# ClimaSens-Touch.net
KiCad netlist of a schematic drawn in Altium Designer
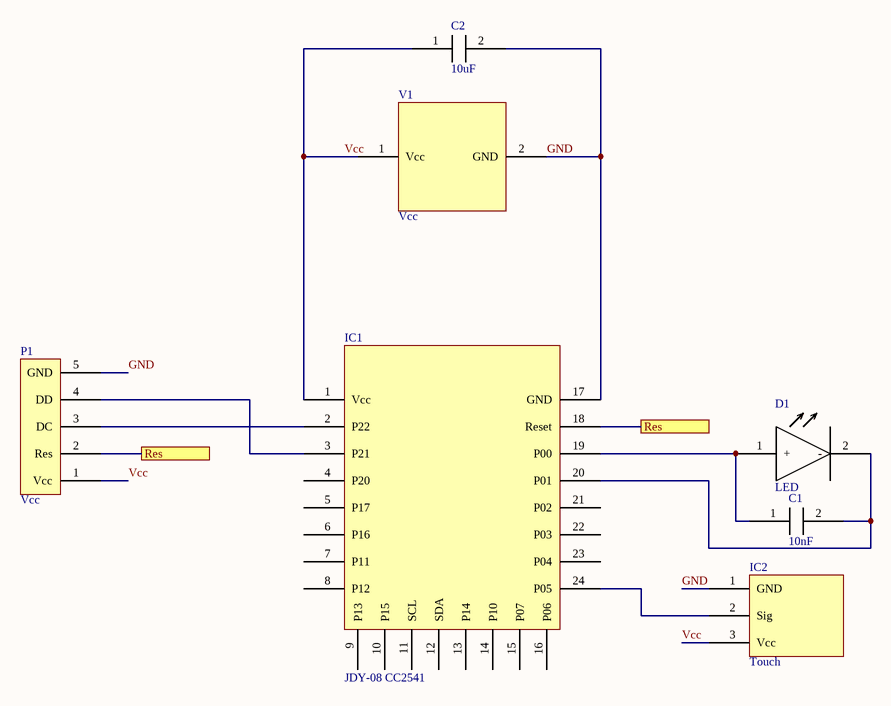
[diagram p0: ClimaSens-Touch.SchDoc]

(export (version "E")
  (design (tool "Eeschema 10.0.6"))
  (components
    (comp (ref "C1") (value "10nF") (footprint "0805") (libsource (lib "ClimaSens-Lib") (part "Capacitator")))
    (comp (ref "C2") (value "10uF") (footprint "0805") (libsource (lib "ClimaSens-Lib") (part "Capacitator")))
    (comp (ref "D1") (value "LED") (footprint "LED 3mm") (libsource (lib "ClimaSens-Lib") (part "LED")))
    (comp (ref "IC1")
      (value "JDY-08 CC2541")
      (footprint "JDY-08 CC2541")
      (libsource (lib "ClimaSens-Lib") (part "JDY-08 CC2541"))
    )
    (comp (ref "IC2") (value "Touch") (footprint "Touch") (libsource (lib "ClimaSens-Lib") (part "Touch")))
    (comp (ref "P1")
      (value "Vcc")
      (footprint "ProgramPort")
      (libsource (lib "ClimaSens-Lib") (part "ProgramPort"))
    )
    (comp (ref "V1")
      (value "Vcc")
      (footprint "Battery-Clip")
      (libsource (lib "ClimaSens-Lib") (part "Battery Clip"))
    )
  )
  (nets
    (net (code "1") (name "/GND") (class "Default")
      (node (ref "C2") (pin "2") (pintype "passive"))
      (node (ref "IC1") (pin "17") (pinfunction "GND_17") (pintype "passive"))
      (node (ref "IC2") (pin "1") (pinfunction "GND_1") (pintype "passive"))
      (node (ref "P1") (pin "5") (pinfunction "GND_5") (pintype "passive"))
      (node (ref "V1") (pin "2") (pinfunction "GND_2") (pintype "passive"))
    )
    (net (code "2") (name "/Res") (class "Default")
      (node (ref "IC1") (pin "18") (pinfunction "Reset_18") (pintype "passive"))
      (node (ref "P1") (pin "2") (pinfunction "Res_2") (pintype "passive"))
    )
    (net (code "3") (name "/Vcc") (class "Default")
      (node (ref "C2") (pin "1") (pintype "passive"))
      (node (ref "IC1") (pin "1") (pinfunction "Vcc_1") (pintype "passive"))
      (node (ref "IC2") (pin "3") (pinfunction "Vcc_3") (pintype "passive"))
      (node (ref "P1") (pin "1") (pinfunction "Vcc_1") (pintype "passive"))
      (node (ref "V1") (pin "1") (pinfunction "Vcc_1") (pintype "passive"))
    )
    (net (code "4") (name "Net-(D1-+)") (class "Default")
      (node (ref "C1") (pin "1") (pintype "passive"))
      (node (ref "D1") (pin "1") (pinfunction "+_1") (pintype "passive"))
      (node (ref "IC1") (pin "19") (pinfunction "P00_19") (pintype "passive"))
    )
    (net (code "5") (name "Net-(D1--)") (class "Default")
      (node (ref "C1") (pin "2") (pintype "passive"))
      (node (ref "D1") (pin "2") (pinfunction "-_2") (pintype "passive"))
      (node (ref "IC1") (pin "20") (pinfunction "P01_20") (pintype "passive"))
    )
    (net (code "6") (name "Net-(IC1-P05)") (class "Default")
      (node (ref "IC1") (pin "24") (pinfunction "P05_24") (pintype "passive"))
      (node (ref "IC2") (pin "2") (pinfunction "Sig_2") (pintype "passive"))
    )
    (net (code "7") (name "Net-(IC1-P21)") (class "Default")
      (node (ref "IC1") (pin "3") (pinfunction "P21_3") (pintype "passive"))
      (node (ref "P1") (pin "4") (pinfunction "DD_4") (pintype "passive"))
    )
    (net (code "8") (name "Net-(IC1-P22)") (class "Default")
      (node (ref "IC1") (pin "2") (pinfunction "P22_2") (pintype "passive"))
      (node (ref "P1") (pin "3") (pinfunction "DC_3") (pintype "passive"))
    )
    (net (code "9") (name "unconnected-(IC1-P02-Pad21)") (class "Default")
      (node (ref "IC1") (pin "21") (pinfunction "P02_21") (pintype "passive"))
    )
    (net (code "10") (name "unconnected-(IC1-P03-Pad22)") (class "Default")
      (node (ref "IC1") (pin "22") (pinfunction "P03_22") (pintype "passive"))
    )
    (net (code "11") (name "unconnected-(IC1-P04-Pad23)") (class "Default")
      (node (ref "IC1") (pin "23") (pinfunction "P04_23") (pintype "passive"))
    )
    (net (code "12") (name "unconnected-(IC1-P06-Pad16)") (class "Default")
      (node (ref "IC1") (pin "16") (pinfunction "P06_16") (pintype "passive"))
    )
    (net (code "13") (name "unconnected-(IC1-P07-Pad15)") (class "Default")
      (node (ref "IC1") (pin "15") (pinfunction "P07_15") (pintype "passive"))
    )
    (net (code "14") (name "unconnected-(IC1-P10-Pad14)") (class "Default")
      (node (ref "IC1") (pin "14") (pinfunction "P10_14") (pintype "passive"))
    )
    (net (code "15") (name "unconnected-(IC1-P11-Pad7)") (class "Default")
      (node (ref "IC1") (pin "7") (pinfunction "P11_7") (pintype "passive"))
    )
    (net (code "16") (name "unconnected-(IC1-P12-Pad8)") (class "Default")
      (node (ref "IC1") (pin "8") (pinfunction "P12_8") (pintype "passive"))
    )
    (net (code "17") (name "unconnected-(IC1-P13-Pad9)") (class "Default")
      (node (ref "IC1") (pin "9") (pinfunction "P13_9") (pintype "passive"))
    )
    (net (code "18") (name "unconnected-(IC1-P14-Pad13)") (class "Default")
      (node (ref "IC1") (pin "13") (pinfunction "P14_13") (pintype "passive"))
    )
    (net (code "19") (name "unconnected-(IC1-P15-Pad10)") (class "Default")
      (node (ref "IC1") (pin "10") (pinfunction "P15_10") (pintype "passive"))
    )
    (net (code "20") (name "unconnected-(IC1-P16-Pad6)") (class "Default")
      (node (ref "IC1") (pin "6") (pinfunction "P16_6") (pintype "passive"))
    )
    (net (code "21") (name "unconnected-(IC1-P17-Pad5)") (class "Default")
      (node (ref "IC1") (pin "5") (pinfunction "P17_5") (pintype "passive"))
    )
    (net (code "22") (name "unconnected-(IC1-P20-Pad4)") (class "Default")
      (node (ref "IC1") (pin "4") (pinfunction "P20_4") (pintype "passive"))
    )
    (net (code "23") (name "unconnected-(IC1-SCL-Pad11)") (class "Default")
      (node (ref "IC1") (pin "11") (pinfunction "SCL_11") (pintype "passive"))
    )
    (net (code "24") (name "unconnected-(IC1-SDA-Pad12)") (class "Default")
      (node (ref "IC1") (pin "12") (pinfunction "SDA_12") (pintype "passive"))
    )
  )
)
